# WS2811_Relais.net
KiCad netlist of a schematic drawn in EAGLE
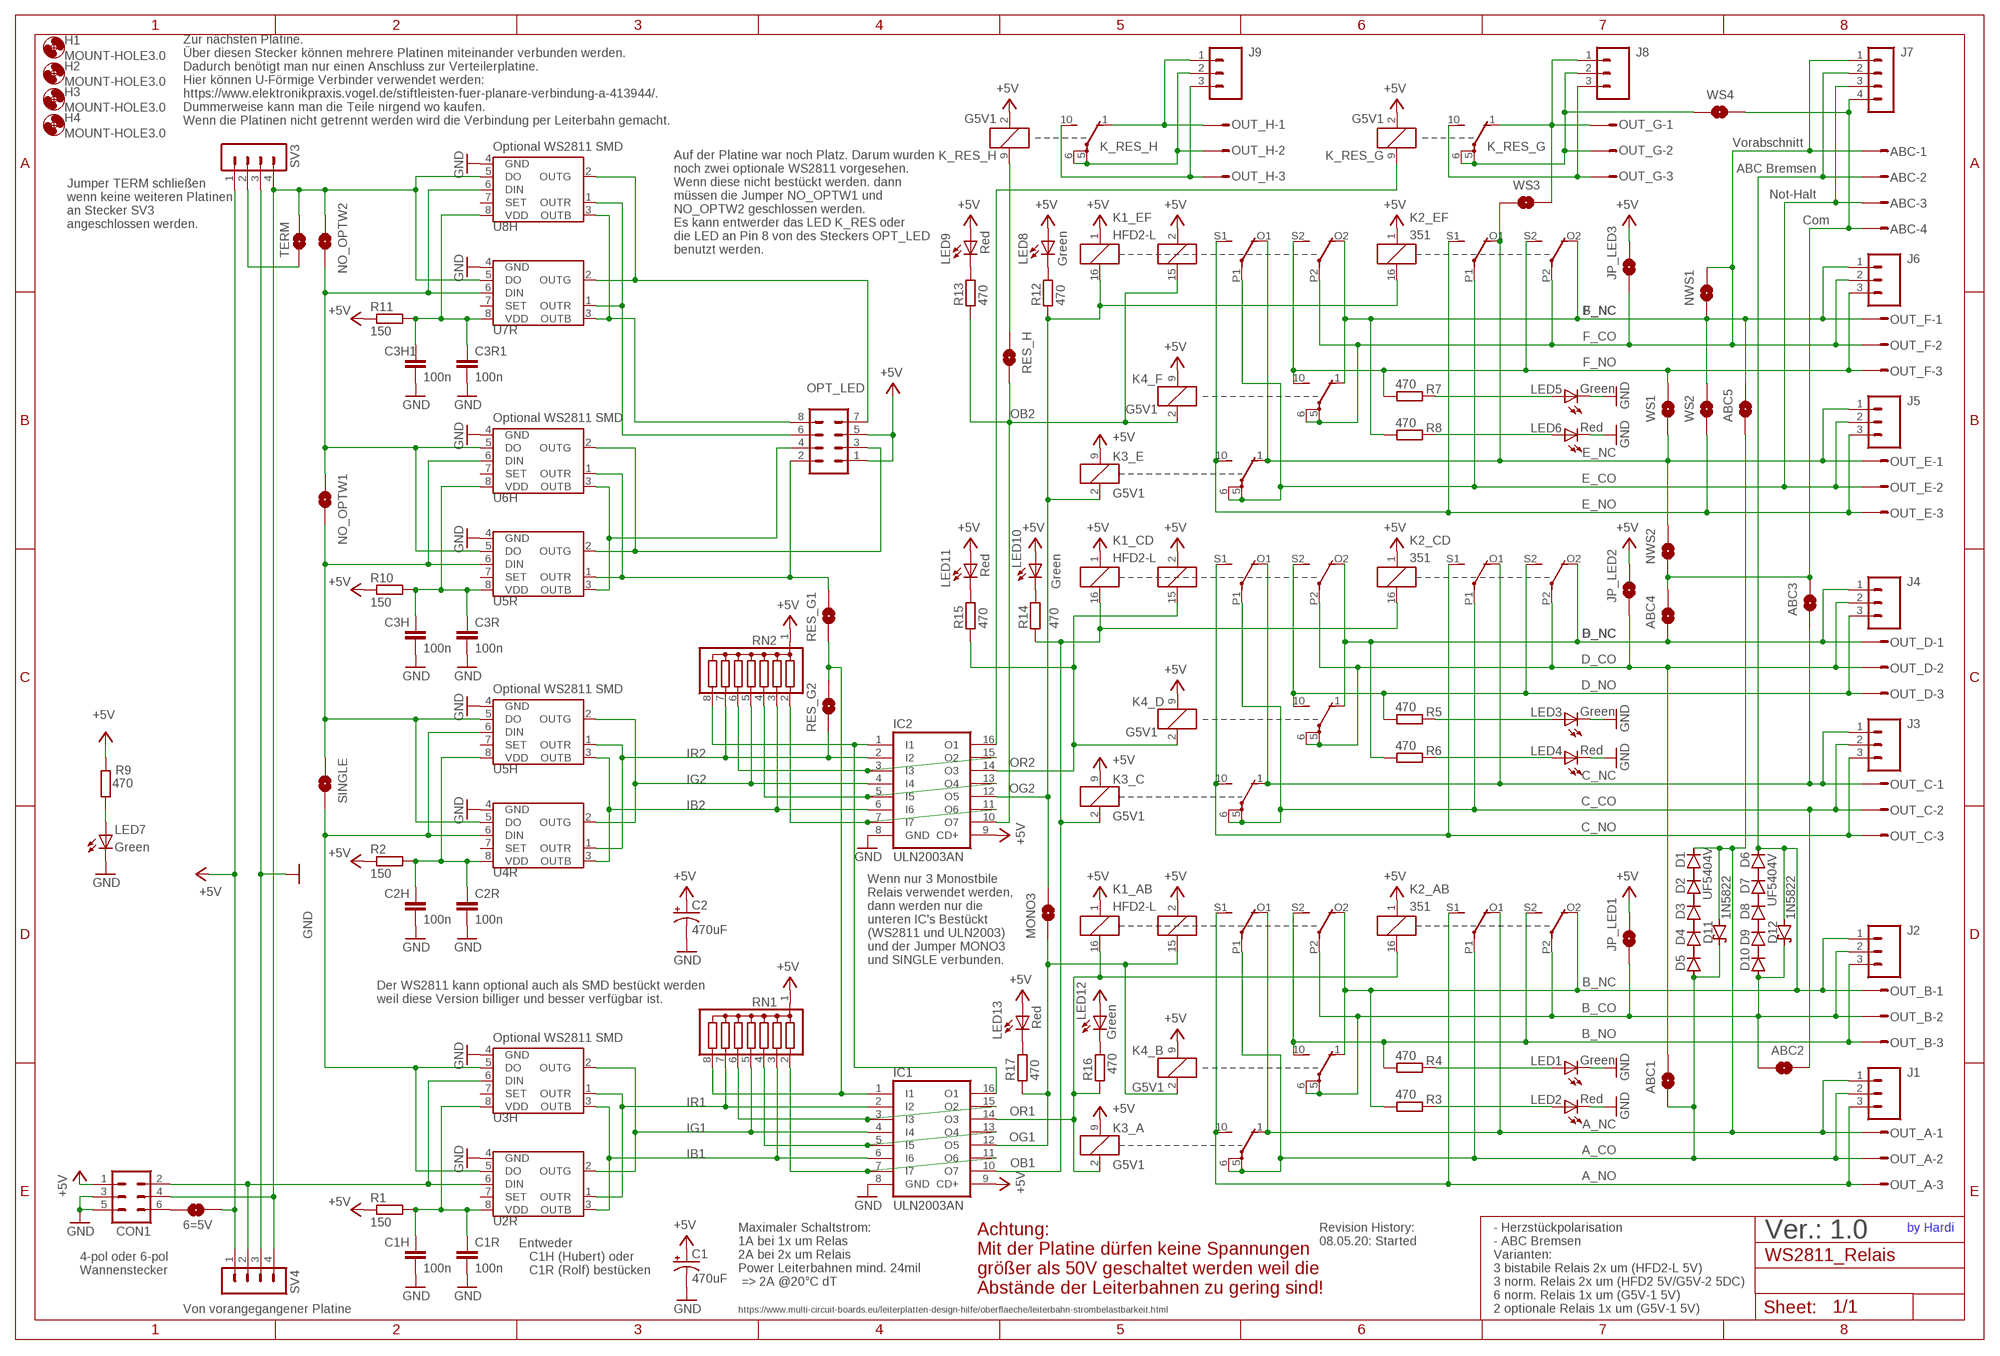
[diagram p0: schematic, sheet 1]

(export (version "E")
  (design (tool "Eeschema 10.0.6"))
  (components
    (comp (ref "6=5V")
      (value "SOLDERJUMPERNO")
      (footprint "eagle-import:SJ_2S-NO")
      (libsource (lib "eagle-import") (part "SOLDERJUMPERNO"))
    )
    (comp (ref "ABC")
      (value "STL1550-4ON_BOARD")
      (footprint "eagle-import:STL1550-4_ON_BOARD")
      (libsource (lib "eagle-import") (part "STL1550-4ON_BOARD"))
    )
    (comp (ref "ABC1")
      (value "SOLDERJUMPERNO")
      (footprint "eagle-import:SJ_2S-NO")
      (libsource (lib "eagle-import") (part "SOLDERJUMPERNO"))
    )
    (comp (ref "ABC2")
      (value "SOLDERJUMPERNO")
      (footprint "eagle-import:SJ_2S-NO")
      (libsource (lib "eagle-import") (part "SOLDERJUMPERNO"))
    )
    (comp (ref "ABC3")
      (value "SOLDERJUMPERNO")
      (footprint "eagle-import:SJ_2S-NO")
      (libsource (lib "eagle-import") (part "SOLDERJUMPERNO"))
    )
    (comp (ref "ABC4")
      (value "SOLDERJUMPERNO")
      (footprint "eagle-import:SJ_2S-NO")
      (libsource (lib "eagle-import") (part "SOLDERJUMPERNO"))
    )
    (comp (ref "ABC5")
      (value "SOLDERJUMPERNO")
      (footprint "eagle-import:SJ_2S-NO")
      (libsource (lib "eagle-import") (part "SOLDERJUMPERNO"))
    )
    (comp (ref "C1")
      (value "470uF")
      (footprint "eagle-import:SPARKFUN-CAPACITORS_CPOL-RADIAL-100UF-25V")
      (libsource (lib "eagle-import") (part "SPARKFUN-CAPACITORS_100UF-25V-20%(PTH)"))
    )
    (comp (ref "C1H")
      (value "100n")
      (footprint "eagle-import:C1206")
      (libsource (lib "eagle-import") (part "C-EUC1206"))
    )
    (comp (ref "C1R")
      (value "100n")
      (footprint "eagle-import:C025-024X044")
      (libsource (lib "eagle-import") (part "C-EU025-024X044"))
    )
    (comp (ref "C2")
      (value "470uF")
      (footprint "eagle-import:SPARKFUN-CAPACITORS_CPOL-RADIAL-100UF-25V")
      (libsource (lib "eagle-import") (part "SPARKFUN-CAPACITORS_100UF-25V-20%(PTH)"))
    )
    (comp (ref "C2H")
      (value "100n")
      (footprint "eagle-import:C1206")
      (libsource (lib "eagle-import") (part "C-EUC1206"))
    )
    (comp (ref "C2R")
      (value "100n")
      (footprint "eagle-import:C025-024X044")
      (libsource (lib "eagle-import") (part "C-EU025-024X044"))
    )
    (comp (ref "C3H")
      (value "100n")
      (footprint "eagle-import:C1206")
      (libsource (lib "eagle-import") (part "C-EUC1206"))
    )
    (comp (ref "C3H1")
      (value "100n")
      (footprint "eagle-import:C1206")
      (libsource (lib "eagle-import") (part "C-EUC1206"))
    )
    (comp (ref "C3R")
      (value "100n")
      (footprint "eagle-import:C025-024X044")
      (libsource (lib "eagle-import") (part "C-EU025-024X044"))
    )
    (comp (ref "C3R1")
      (value "100n")
      (footprint "eagle-import:C025-024X044")
      (libsource (lib "eagle-import") (part "C-EU025-024X044"))
    )
    (comp (ref "CON1")
      (value "ML6")
      (footprint "eagle-import:ML6")
      (libsource (lib "eagle-import") (part "ML6"))
    )
    (comp (ref "D1")
      (value "UF5404V")
      (footprint "eagle-import:DO201-15-V")
      (libsource (lib "eagle-import") (part "UF5404V"))
    )
    (comp (ref "D2")
      (value "UF5404V")
      (footprint "eagle-import:DO201-15-V")
      (libsource (lib "eagle-import") (part "UF5404V"))
    )
    (comp (ref "D3")
      (value "UF5404V")
      (footprint "eagle-import:DO201-15-V")
      (libsource (lib "eagle-import") (part "UF5404V"))
    )
    (comp (ref "D4")
      (value "UF5404V")
      (footprint "eagle-import:DO201-15-V")
      (libsource (lib "eagle-import") (part "UF5404V"))
    )
    (comp (ref "D5")
      (value "UF5404V")
      (footprint "eagle-import:DO201-15-V")
      (libsource (lib "eagle-import") (part "UF5404V"))
    )
    (comp (ref "D6")
      (value "UF5404V")
      (footprint "eagle-import:DO201-15-V")
      (libsource (lib "eagle-import") (part "UF5404V"))
    )
    (comp (ref "D7")
      (value "UF5404V")
      (footprint "eagle-import:DO201-15-V")
      (libsource (lib "eagle-import") (part "UF5404V"))
    )
    (comp (ref "D8")
      (value "UF5404V")
      (footprint "eagle-import:DO201-15-V")
      (libsource (lib "eagle-import") (part "UF5404V"))
    )
    (comp (ref "D9")
      (value "UF5404V")
      (footprint "eagle-import:DO201-15-V")
      (libsource (lib "eagle-import") (part "UF5404V"))
    )
    (comp (ref "D10")
      (value "UF5404V")
      (footprint "eagle-import:DO201-15-V")
      (libsource (lib "eagle-import") (part "UF5404V"))
    )
    (comp (ref "D11")
      (value "1N5822")
      (footprint "eagle-import:DO41-7.6")
      (libsource (lib "eagle-import") (part "1N5822"))
    )
    (comp (ref "D12")
      (value "1N5822")
      (footprint "eagle-import:DO41-7.6")
      (libsource (lib "eagle-import") (part "1N5822"))
    )
    (comp (ref "H1")
      (value "MOUNT-HOLE3.0")
      (footprint "eagle-import:3,0")
      (libsource (lib "eagle-import") (part "MOUNT-HOLE3.0"))
    )
    (comp (ref "H2")
      (value "MOUNT-HOLE3.0")
      (footprint "eagle-import:3,0")
      (libsource (lib "eagle-import") (part "MOUNT-HOLE3.0"))
    )
    (comp (ref "H3")
      (value "MOUNT-HOLE3.0")
      (footprint "eagle-import:3,0")
      (libsource (lib "eagle-import") (part "MOUNT-HOLE3.0"))
    )
    (comp (ref "H4")
      (value "MOUNT-HOLE3.0")
      (footprint "eagle-import:3,0")
      (libsource (lib "eagle-import") (part "MOUNT-HOLE3.0"))
    )
    (comp (ref "IC1")
      (value "ULN2003AN")
      (footprint "eagle-import:DIL16")
      (libsource (lib "eagle-import") (part "ULN2003AN"))
    )
    (comp (ref "IC2")
      (value "ULN2003AN")
      (footprint "eagle-import:DIL16")
      (libsource (lib "eagle-import") (part "ULN2003AN"))
    )
    (comp (ref "J1")
      (value "M03PTH")
      (footprint "eagle-import:1X03")
      (libsource (lib "eagle-import") (part "M03PTH"))
    )
    (comp (ref "J2")
      (value "M03PTH")
      (footprint "eagle-import:1X03")
      (libsource (lib "eagle-import") (part "M03PTH"))
    )
    (comp (ref "J3")
      (value "M03PTH")
      (footprint "eagle-import:1X03")
      (libsource (lib "eagle-import") (part "M03PTH"))
    )
    (comp (ref "J4")
      (value "M03PTH")
      (footprint "eagle-import:1X03")
      (libsource (lib "eagle-import") (part "M03PTH"))
    )
    (comp (ref "J5")
      (value "M03PTH")
      (footprint "eagle-import:1X03")
      (libsource (lib "eagle-import") (part "M03PTH"))
    )
    (comp (ref "J6")
      (value "M03PTH")
      (footprint "eagle-import:1X03")
      (libsource (lib "eagle-import") (part "M03PTH"))
    )
    (comp (ref "J7")
      (value "MA04-1")
      (footprint "eagle-import:MA04-1")
      (libsource (lib "eagle-import") (part "MA04-1"))
    )
    (comp (ref "J8")
      (value "M03PTH")
      (footprint "eagle-import:1X03")
      (libsource (lib "eagle-import") (part "M03PTH"))
    )
    (comp (ref "J9")
      (value "M03PTH")
      (footprint "eagle-import:1X03")
      (libsource (lib "eagle-import") (part "M03PTH"))
    )
    (comp (ref "JP_LED1")
      (value "SOLDERJUMPERNO")
      (footprint "eagle-import:SJ_2S-NO")
      (libsource (lib "eagle-import") (part "SOLDERJUMPERNO"))
    )
    (comp (ref "JP_LED2")
      (value "SOLDERJUMPERNO")
      (footprint "eagle-import:SJ_2S-NO")
      (libsource (lib "eagle-import") (part "SOLDERJUMPERNO"))
    )
    (comp (ref "JP_LED3")
      (value "SOLDERJUMPERNO")
      (footprint "eagle-import:SJ_2S-NO")
      (libsource (lib "eagle-import") (part "SOLDERJUMPERNO"))
    )
    (comp (ref "K1_AB")
      (value "HFD2-L")
      (footprint "eagle-import:HFD2-L")
      (libsource (lib "eagle-import") (part "HFD2-L"))
    )
    (comp (ref "K1_CD")
      (value "HFD2-L")
      (footprint "eagle-import:HFD2-L")
      (libsource (lib "eagle-import") (part "HFD2-L"))
    )
    (comp (ref "K1_EF")
      (value "HFD2-L")
      (footprint "eagle-import:HFD2-L")
      (libsource (lib "eagle-import") (part "HFD2-L"))
    )
    (comp (ref "K2_AB")
      (value "351")
      (footprint "eagle-import:351")
      (libsource (lib "eagle-import") (part "351"))
    )
    (comp (ref "K2_CD")
      (value "351")
      (footprint "eagle-import:351")
      (libsource (lib "eagle-import") (part "351"))
    )
    (comp (ref "K2_EF")
      (value "351")
      (footprint "eagle-import:351")
      (libsource (lib "eagle-import") (part "351"))
    )
    (comp (ref "K3_A")
      (value "G5V1")
      (footprint "eagle-import:G5V1")
      (fields (field (name "MPN") "G5V-1-DC24"))
      (libsource (lib "eagle-import") (part "G5V1"))
    )
    (comp (ref "K3_C")
      (value "G5V1")
      (footprint "eagle-import:G5V1")
      (fields (field (name "MPN") "G5V-1-DC24"))
      (libsource (lib "eagle-import") (part "G5V1"))
    )
    (comp (ref "K3_E")
      (value "G5V1")
      (footprint "eagle-import:G5V1")
      (fields (field (name "MPN") "G5V-1-DC24"))
      (libsource (lib "eagle-import") (part "G5V1"))
    )
    (comp (ref "K4_B")
      (value "G5V1")
      (footprint "eagle-import:G5V1")
      (fields (field (name "MPN") "G5V-1-DC24"))
      (libsource (lib "eagle-import") (part "G5V1"))
    )
    (comp (ref "K4_D")
      (value "G5V1")
      (footprint "eagle-import:G5V1")
      (fields (field (name "MPN") "G5V-1-DC24"))
      (libsource (lib "eagle-import") (part "G5V1"))
    )
    (comp (ref "K4_F")
      (value "G5V1")
      (footprint "eagle-import:G5V1")
      (fields (field (name "MPN") "G5V-1-DC24"))
      (libsource (lib "eagle-import") (part "G5V1"))
    )
    (comp (ref "K_RES_G")
      (value "G5V1")
      (footprint "eagle-import:G5V1")
      (fields (field (name "MPN") "G5V-1-DC24"))
      (libsource (lib "eagle-import") (part "G5V1"))
    )
    (comp (ref "K_RES_H")
      (value "G5V1")
      (footprint "eagle-import:G5V1")
      (fields (field (name "MPN") "G5V-1-DC24"))
      (libsource (lib "eagle-import") (part "G5V1"))
    )
    (comp (ref "LED1")
      (value "Green")
      (footprint "eagle-import:LED3MM")
      (libsource (lib "eagle-import") (part "LED3MM"))
    )
    (comp (ref "LED2")
      (value "Red")
      (footprint "eagle-import:LED3MM")
      (libsource (lib "eagle-import") (part "LED3MM"))
    )
    (comp (ref "LED3")
      (value "Green")
      (footprint "eagle-import:LED3MM")
      (libsource (lib "eagle-import") (part "LED3MM"))
    )
    (comp (ref "LED4")
      (value "Red")
      (footprint "eagle-import:LED3MM")
      (libsource (lib "eagle-import") (part "LED3MM"))
    )
    (comp (ref "LED5")
      (value "Green")
      (footprint "eagle-import:LED3MM")
      (libsource (lib "eagle-import") (part "LED3MM"))
    )
    (comp (ref "LED6")
      (value "Red")
      (footprint "eagle-import:LED3MM")
      (libsource (lib "eagle-import") (part "LED3MM"))
    )
    (comp (ref "LED7")
      (value "Green")
      (footprint "eagle-import:LED3MM")
      (libsource (lib "eagle-import") (part "LED3MM"))
    )
    (comp (ref "LED8")
      (value "Green")
      (footprint "eagle-import:LED3MM")
      (libsource (lib "eagle-import") (part "LED3MM"))
    )
    (comp (ref "LED9")
      (value "Red")
      (footprint "eagle-import:LED3MM")
      (libsource (lib "eagle-import") (part "LED3MM"))
    )
    (comp (ref "LED10")
      (value "Green")
      (footprint "eagle-import:LED3MM")
      (libsource (lib "eagle-import") (part "LED3MM"))
    )
    (comp (ref "LED11")
      (value "Red")
      (footprint "eagle-import:LED3MM")
      (libsource (lib "eagle-import") (part "LED3MM"))
    )
    (comp (ref "LED12")
      (value "Green")
      (footprint "eagle-import:LED3MM")
      (libsource (lib "eagle-import") (part "LED3MM"))
    )
    (comp (ref "LED13")
      (value "Red")
      (footprint "eagle-import:LED3MM")
      (libsource (lib "eagle-import") (part "LED3MM"))
    )
    (comp (ref "MONO3")
      (value "SOLDERJUMPERNO")
      (footprint "eagle-import:SJ_2S-NO")
      (libsource (lib "eagle-import") (part "SOLDERJUMPERNO"))
    )
    (comp (ref "NO_OPTW1")
      (value "SOLDERJUMPERNO")
      (footprint "eagle-import:SJ_2S-NO")
      (libsource (lib "eagle-import") (part "SOLDERJUMPERNO"))
    )
    (comp (ref "NO_OPTW2")
      (value "SOLDERJUMPERNO")
      (footprint "eagle-import:SJ_2S-NO")
      (libsource (lib "eagle-import") (part "SOLDERJUMPERNO"))
    )
    (comp (ref "NWS1")
      (value "SOLDERJUMPERNO")
      (footprint "eagle-import:SJ_2S-NO")
      (libsource (lib "eagle-import") (part "SOLDERJUMPERNO"))
    )
    (comp (ref "NWS2")
      (value "SOLDERJUMPERNO")
      (footprint "eagle-import:SJ_2S-NO")
      (libsource (lib "eagle-import") (part "SOLDERJUMPERNO"))
    )
    (comp (ref "OPT_LED")
      (value "CON-HARTING-ML_ML08")
      (footprint "eagle-import:CON-HARTING-ML_ML08")
      (libsource (lib "eagle-import") (part "CON-HARTING-ML_ML08"))
    )
    (comp (ref "OUT_A")
      (value "STL1550-3")
      (footprint "eagle-import:STL1550-3_ON_BOARD")
      (libsource (lib "eagle-import") (part "STL1550-3"))
    )
    (comp (ref "OUT_B")
      (value "STL1550-3")
      (footprint "eagle-import:STL1550-3_ON_BOARD")
      (libsource (lib "eagle-import") (part "STL1550-3"))
    )
    (comp (ref "OUT_C")
      (value "STL1550-3")
      (footprint "eagle-import:STL1550-3_ON_BOARD")
      (libsource (lib "eagle-import") (part "STL1550-3"))
    )
    (comp (ref "OUT_D")
      (value "STL1550-3")
      (footprint "eagle-import:STL1550-3_ON_BOARD")
      (libsource (lib "eagle-import") (part "STL1550-3"))
    )
    (comp (ref "OUT_E")
      (value "STL1550-3")
      (footprint "eagle-import:STL1550-3_ON_BOARD")
      (libsource (lib "eagle-import") (part "STL1550-3"))
    )
    (comp (ref "OUT_F")
      (value "STL1550-3")
      (footprint "eagle-import:STL1550-3_ON_BOARD")
      (libsource (lib "eagle-import") (part "STL1550-3"))
    )
    (comp (ref "OUT_G")
      (value "STL1550-3")
      (footprint "eagle-import:STL1550-3_ON_BOARD")
      (libsource (lib "eagle-import") (part "STL1550-3"))
    )
    (comp (ref "OUT_H")
      (value "STL1550-3")
      (footprint "eagle-import:STL1550-3_ON_BOARD")
      (libsource (lib "eagle-import") (part "STL1550-3"))
    )
    (comp (ref "R1")
      (value "150")
      (footprint "eagle-import:RCL_0207_2V")
      (libsource (lib "eagle-import") (part "RCL_R-EU_0207/2V"))
    )
    (comp (ref "R2")
      (value "150")
      (footprint "eagle-import:RCL_0207_2V")
      (libsource (lib "eagle-import") (part "RCL_R-EU_0207/2V"))
    )
    (comp (ref "R3")
      (value "470")
      (footprint "eagle-import:0204_2V")
      (libsource (lib "eagle-import") (part "R0204/2V"))
    )
    (comp (ref "R4")
      (value "470")
      (footprint "eagle-import:0204_2V")
      (libsource (lib "eagle-import") (part "R0204/2V"))
    )
    (comp (ref "R5")
      (value "470")
      (footprint "eagle-import:0204_2V")
      (libsource (lib "eagle-import") (part "R0204/2V"))
    )
    (comp (ref "R6")
      (value "470")
      (footprint "eagle-import:0204_2V")
      (libsource (lib "eagle-import") (part "R0204/2V"))
    )
    (comp (ref "R7")
      (value "470")
      (footprint "eagle-import:0204_2V")
      (libsource (lib "eagle-import") (part "R0204/2V"))
    )
    (comp (ref "R8")
      (value "470")
      (footprint "eagle-import:0204_2V")
      (libsource (lib "eagle-import") (part "R0204/2V"))
    )
    (comp (ref "R9")
      (value "470")
      (footprint "eagle-import:0204_2V")
      (libsource (lib "eagle-import") (part "R0204/2V"))
    )
    (comp (ref "R10")
      (value "150")
      (footprint "eagle-import:RCL_0207_2V")
      (libsource (lib "eagle-import") (part "RCL_R-EU_0207/2V"))
    )
    (comp (ref "R11")
      (value "150")
      (footprint "eagle-import:RCL_0207_2V")
      (libsource (lib "eagle-import") (part "RCL_R-EU_0207/2V"))
    )
    (comp (ref "R12")
      (value "470")
      (footprint "eagle-import:0204_2V")
      (libsource (lib "eagle-import") (part "R0204/2V"))
    )
    (comp (ref "R13")
      (value "470")
      (footprint "eagle-import:0204_2V")
      (libsource (lib "eagle-import") (part "R0204/2V"))
    )
    (comp (ref "R14")
      (value "470")
      (footprint "eagle-import:0204_2V")
      (libsource (lib "eagle-import") (part "R0204/2V"))
    )
    (comp (ref "R15")
      (value "470")
      (footprint "eagle-import:0204_2V")
      (libsource (lib "eagle-import") (part "R0204/2V"))
    )
    (comp (ref "R16")
      (value "470")
      (footprint "eagle-import:0204_2V")
      (libsource (lib "eagle-import") (part "R0204/2V"))
    )
    (comp (ref "R17")
      (value "470")
      (footprint "eagle-import:0204_2V")
      (libsource (lib "eagle-import") (part "R0204/2V"))
    )
    (comp (ref "RES_G1")
      (value "SOLDERJUMPERNO")
      (footprint "eagle-import:SJ_2S-NO")
      (libsource (lib "eagle-import") (part "SOLDERJUMPERNO"))
    )
    (comp (ref "RES_G2")
      (value "SOLDERJUMPERNO")
      (footprint "eagle-import:SJ_2S-NO")
      (libsource (lib "eagle-import") (part "SOLDERJUMPERNO"))
    )
    (comp (ref "RES_H")
      (value "SOLDERJUMPERNO")
      (footprint "eagle-import:SJ_2S-NO")
      (libsource (lib "eagle-import") (part "SOLDERJUMPERNO"))
    )
    (comp (ref "RN1")
      (value "G07R")
      (footprint "eagle-import:SIL8")
      (libsource (lib "eagle-import") (part "G07R"))
    )
    (comp (ref "RN2")
      (value "G07R")
      (footprint "eagle-import:SIL8")
      (libsource (lib "eagle-import") (part "G07R"))
    )
    (comp (ref "SINGLE")
      (value "SOLDERJUMPERNO")
      (footprint "eagle-import:SJ_2S-NO")
      (libsource (lib "eagle-import") (part "SOLDERJUMPERNO"))
    )
    (comp (ref "SV3")
      (value "MA04-1")
      (footprint "eagle-import:MA04-1")
      (libsource (lib "eagle-import") (part "MA04-1"))
    )
    (comp (ref "SV4")
      (value "MA04-1")
      (footprint "eagle-import:MA04-1")
      (libsource (lib "eagle-import") (part "MA04-1"))
    )
    (comp (ref "TERM")
      (value "SOLDERJUMPERNO")
      (footprint "eagle-import:SJ_2S-NO")
      (libsource (lib "eagle-import") (part "SOLDERJUMPERNO"))
    )
    (comp (ref "U2R")
      (value "WS2811")
      (footprint "eagle-import:S3PO_MODUL_WS2811_SOUND_MP3-TF-16P_WS2811_AND_ATTINY_WS2811_DIP08")
      (libsource (lib "eagle-import") (part "S3PO_MODUL_WS2811_SOUND_MP3-TF-16P_WS2811_AND_ATTINY_WS2811-ICTINY45-20-DIP"))
    )
    (comp (ref "U3H")
      (value "WS2811 SOT-8")
      (footprint "eagle-import:SOP8")
      (libsource (lib "eagle-import") (part "S3PO_MODUL_WS2811_SOUND_MP3-TF-16P_WS2811_AND_ATTINY_WS2811-ICSOP8"))
    )
    (comp (ref "U4R")
      (value "WS2811")
      (footprint "eagle-import:S3PO_MODUL_WS2811_SOUND_MP3-TF-16P_WS2811_AND_ATTINY_WS2811_DIP08")
      (libsource (lib "eagle-import") (part "S3PO_MODUL_WS2811_SOUND_MP3-TF-16P_WS2811_AND_ATTINY_WS2811-ICTINY45-20-DIP"))
    )
    (comp (ref "U5H")
      (value "WS2811 SOT-8")
      (footprint "eagle-import:SOP8")
      (libsource (lib "eagle-import") (part "S3PO_MODUL_WS2811_SOUND_MP3-TF-16P_WS2811_AND_ATTINY_WS2811-ICSOP8"))
    )
    (comp (ref "U5R")
      (value "WS2811")
      (footprint "eagle-import:S3PO_MODUL_WS2811_SOUND_MP3-TF-16P_WS2811_AND_ATTINY_WS2811_DIP08")
      (libsource (lib "eagle-import") (part "S3PO_MODUL_WS2811_SOUND_MP3-TF-16P_WS2811_AND_ATTINY_WS2811-ICTINY45-20-DIP"))
    )
    (comp (ref "U6H")
      (value "WS2811 SOT-8")
      (footprint "eagle-import:SOP8")
      (libsource (lib "eagle-import") (part "S3PO_MODUL_WS2811_SOUND_MP3-TF-16P_WS2811_AND_ATTINY_WS2811-ICSOP8"))
    )
    (comp (ref "U7R")
      (value "WS2811")
      (footprint "eagle-import:S3PO_MODUL_WS2811_SOUND_MP3-TF-16P_WS2811_AND_ATTINY_WS2811_DIP08")
      (libsource (lib "eagle-import") (part "S3PO_MODUL_WS2811_SOUND_MP3-TF-16P_WS2811_AND_ATTINY_WS2811-ICTINY45-20-DIP"))
    )
    (comp (ref "U8H")
      (value "WS2811 SOT-8")
      (footprint "eagle-import:SOP8")
      (libsource (lib "eagle-import") (part "S3PO_MODUL_WS2811_SOUND_MP3-TF-16P_WS2811_AND_ATTINY_WS2811-ICSOP8"))
    )
    (comp (ref "WS1")
      (value "SOLDERJUMPERNO")
      (footprint "eagle-import:SJ_2S-NO")
      (libsource (lib "eagle-import") (part "SOLDERJUMPERNO"))
    )
    (comp (ref "WS2")
      (value "SOLDERJUMPERNO")
      (footprint "eagle-import:SJ_2S-NO")
      (libsource (lib "eagle-import") (part "SOLDERJUMPERNO"))
    )
    (comp (ref "WS3")
      (value "SOLDERJUMPERNO")
      (footprint "eagle-import:SJ_2S-NO")
      (libsource (lib "eagle-import") (part "SOLDERJUMPERNO"))
    )
    (comp (ref "WS4")
      (value "SOLDERJUMPERNO")
      (footprint "eagle-import:SJ_2S-NO")
      (libsource (lib "eagle-import") (part "SOLDERJUMPERNO"))
    )
  )
  (nets
    (net (code "1") (name "+5V") (class "Default")
      (node (ref "6=5V") (pin "2") (pinfunction "2_2") (pintype "passive"))
      (node (ref "C1") (pin "1") (pinfunction "+_1") (pintype "passive"))
      (node (ref "C2") (pin "1") (pinfunction "+_1") (pintype "passive"))
      (node (ref "CON1") (pin "1") (pinfunction "1_1") (pintype "passive"))
      (node (ref "IC1") (pin "9") (pinfunction "CD+_9") (pintype "passive"))
      (node (ref "IC2") (pin "9") (pinfunction "CD+_9") (pintype "passive"))
      (node (ref "JP_LED1") (pin "2") (pinfunction "2_2") (pintype "passive"))
      (node (ref "JP_LED2") (pin "2") (pinfunction "2_2") (pintype "passive"))
      (node (ref "JP_LED3") (pin "2") (pinfunction "2_2") (pintype "passive"))
      (node (ref "K1_AB") (pin "1") (pinfunction "1_1") (pintype "passive"))
      (node (ref "K1_AB") (pin "2") (pinfunction "3_2") (pintype "passive"))
      (node (ref "K1_CD") (pin "1") (pinfunction "1_1") (pintype "passive"))
      (node (ref "K1_CD") (pin "2") (pinfunction "3_2") (pintype "passive"))
      (node (ref "K1_EF") (pin "1") (pinfunction "1_1") (pintype "passive"))
      (node (ref "K1_EF") (pin "2") (pinfunction "3_2") (pintype "passive"))
      (node (ref "K2_AB") (pin "1") (pinfunction "1_1") (pintype "passive"))
      (node (ref "K2_CD") (pin "1") (pinfunction "1_1") (pintype "passive"))
      (node (ref "K2_EF") (pin "1") (pinfunction "1_1") (pintype "passive"))
      (node (ref "K3_A") (pin "9") (pinfunction "2_9") (pintype "passive"))
      (node (ref "K3_C") (pin "9") (pinfunction "2_9") (pintype "passive"))
      (node (ref "K3_E") (pin "9") (pinfunction "2_9") (pintype "passive"))
      (node (ref "K4_B") (pin "9") (pinfunction "2_9") (pintype "passive"))
      (node (ref "K4_D") (pin "9") (pinfunction "2_9") (pintype "passive"))
      (node (ref "K4_F") (pin "9") (pinfunction "2_9") (pintype "passive"))
      (node (ref "K_RES_G") (pin "2") (pinfunction "1_2") (pintype "passive"))
      (node (ref "K_RES_H") (pin "2") (pinfunction "1_2") (pintype "passive"))
      (node (ref "LED10") (pin "A") (pinfunction "A_A") (pintype "passive"))
      (node (ref "LED11") (pin "A") (pinfunction "A_A") (pintype "passive"))
      (node (ref "LED12") (pin "A") (pinfunction "A_A") (pintype "passive"))
      (node (ref "LED13") (pin "A") (pinfunction "A_A") (pintype "passive"))
      (node (ref "LED8") (pin "A") (pinfunction "A_A") (pintype "passive"))
      (node (ref "LED9") (pin "A") (pinfunction "A_A") (pintype "passive"))
      (node (ref "OPT_LED") (pin "1") (pinfunction "1_1") (pintype "passive"))
      (node (ref "OPT_LED") (pin "5") (pinfunction "5_5") (pintype "passive"))
      (node (ref "R1") (pin "1") (pinfunction "1_1") (pintype "passive"))
      (node (ref "R10") (pin "1") (pinfunction "1_1") (pintype "passive"))
      (node (ref "R11") (pin "1") (pinfunction "1_1") (pintype "passive"))
      (node (ref "R2") (pin "1") (pinfunction "1_1") (pintype "passive"))
      (node (ref "R9") (pin "1") (pinfunction "1_1") (pintype "passive"))
      (node (ref "RN1") (pin "1") (pinfunction "1_1") (pintype "passive"))
      (node (ref "RN2") (pin "1") (pinfunction "1_1") (pintype "passive"))
      (node (ref "SV3") (pin "1") (pinfunction "1_1") (pintype "passive"))
      (node (ref "SV4") (pin "1") (pinfunction "1_1") (pintype "passive"))
    )
    (net (code "2") (name "/A_CO") (class "Default")
      (node (ref "ABC1") (pin "1") (pinfunction "1_1") (pintype "passive"))
      (node (ref "D11") (pin "C") (pinfunction "C_C") (pintype "passive"))
      (node (ref "D5") (pin "A") (pinfunction "A_A") (pintype "passive"))
      (node (ref "J1") (pin "2") (pinfunction "2_2") (pintype "passive"))
      (node (ref "K1_AB") (pin "P1") (pinfunction "P_P1") (pintype "passive"))
      (node (ref "K2_AB") (pin "P1") (pinfunction "P_P1") (pintype "passive"))
      (node (ref "K3_A") (pin "5") (pinfunction "P_5") (pintype "passive"))
      (node (ref "K3_A") (pin "6") (pinfunction "P_6") (pintype "passive"))
      (node (ref "OUT_A") (pin "2") (pinfunction "S_2") (pintype "passive"))
    )
    (net (code "3") (name "/A_NC") (class "Default")
      (node (ref "ABC5") (pin "2") (pinfunction "2_2") (pintype "passive"))
      (node (ref "D1") (pin "C") (pinfunction "C_C") (pintype "passive"))
      (node (ref "D11") (pin "A") (pinfunction "A_A") (pintype "passive"))
      (node (ref "J1") (pin "1") (pinfunction "1_1") (pintype "passive"))
      (node (ref "K1_AB") (pin "O1") (pinfunction "O_O1") (pintype "passive"))
      (node (ref "K2_AB") (pin "O1") (pinfunction "O_O1") (pintype "passive"))
      (node (ref "K3_A") (pin "1") (pinfunction "O_1") (pintype "passive"))
      (node (ref "OUT_A") (pin "1") (pinfunction "S_1") (pintype "passive"))
    )
    (net (code "4") (name "/A_NO") (class "Default")
      (node (ref "J1") (pin "3") (pinfunction "3_3") (pintype "passive"))
      (node (ref "K1_AB") (pin "S1") (pinfunction "S_S1") (pintype "passive"))
      (node (ref "K2_AB") (pin "S1") (pinfunction "S_S1") (pintype "passive"))
      (node (ref "K3_A") (pin "10") (pinfunction "S_10") (pintype "passive"))
      (node (ref "OUT_A") (pin "3") (pinfunction "S_3") (pintype "passive"))
    )
    (net (code "5") (name "/B_CO") (class "Default")
      (node (ref "ABC2") (pin "1") (pinfunction "1_1") (pintype "passive"))
      (node (ref "D10") (pin "A") (pinfunction "A_A") (pintype "passive"))
      (node (ref "D12") (pin "C") (pinfunction "C_C") (pintype "passive"))
      (node (ref "J2") (pin "2") (pinfunction "2_2") (pintype "passive"))
      (node (ref "JP_LED1") (pin "1") (pinfunction "1_1") (pintype "passive"))
      (node (ref "K1_AB") (pin "P2") (pinfunction "P_P2") (pintype "passive"))
      (node (ref "K2_AB") (pin "P2") (pinfunction "P_P2") (pintype "passive"))
      (node (ref "K4_B") (pin "5") (pinfunction "P_5") (pintype "passive"))
      (node (ref "K4_B") (pin "6") (pinfunction "P_6") (pintype "passive"))
      (node (ref "OUT_B") (pin "2") (pinfunction "S_2") (pintype "passive"))
    )
    (net (code "6") (name "/B_NC") (class "Default")
      (node (ref "ABC") (pin "2") (pinfunction "S_2") (pintype "passive"))
      (node (ref "D12") (pin "A") (pinfunction "A_A") (pintype "passive"))
      (node (ref "D6") (pin "C") (pinfunction "C_C") (pintype "passive"))
      (node (ref "J2") (pin "1") (pinfunction "1_1") (pintype "passive"))
      (node (ref "J7") (pin "2") (pinfunction "2_2") (pintype "passive"))
      (node (ref "K1_AB") (pin "O2") (pinfunction "O_O2") (pintype "passive"))
      (node (ref "K2_AB") (pin "O2") (pinfunction "O_O2") (pintype "passive"))
      (node (ref "K4_B") (pin "1") (pinfunction "O_1") (pintype "passive"))
      (node (ref "OUT_B") (pin "1") (pinfunction "S_1") (pintype "passive"))
      (node (ref "R3") (pin "2") (pinfunction "2_2") (pintype "passive"))
    )
    (net (code "7") (name "/B_NO") (class "Default")
      (node (ref "J2") (pin "3") (pinfunction "3_3") (pintype "passive"))
      (node (ref "K1_AB") (pin "S2") (pinfunction "S_S2") (pintype "passive"))
      (node (ref "K2_AB") (pin "S2") (pinfunction "S_S2") (pintype "passive"))
      (node (ref "K4_B") (pin "10") (pinfunction "S_10") (pintype "passive"))
      (node (ref "OUT_B") (pin "3") (pinfunction "S_3") (pintype "passive"))
      (node (ref "R4") (pin "2") (pinfunction "2_2") (pintype "passive"))
    )
    (net (code "8") (name "/C_CO") (class "Default")
      (node (ref "ABC2") (pin "2") (pinfunction "2_2") (pintype "passive"))
      (node (ref "J3") (pin "2") (pinfunction "2_2") (pintype "passive"))
      (node (ref "K1_CD") (pin "P1") (pinfunction "P_P1") (pintype "passive"))
      (node (ref "K2_CD") (pin "P1") (pinfunction "P_P1") (pintype "passive"))
      (node (ref "K3_C") (pin "5") (pinfunction "P_5") (pintype "passive"))
      (node (ref "K3_C") (pin "6") (pinfunction "P_6") (pintype "passive"))
      (node (ref "OUT_C") (pin "2") (pinfunction "S_2") (pintype "passive"))
    )
    (net (code "9") (name "/C_NC") (class "Default")
      (node (ref "ABC3") (pin "2") (pinfunction "2_2") (pintype "passive"))
      (node (ref "J3") (pin "1") (pinfunction "1_1") (pintype "passive"))
      (node (ref "K1_CD") (pin "O1") (pinfunction "O_O1") (pintype "passive"))
      (node (ref "K2_CD") (pin "O1") (pinfunction "O_O1") (pintype "passive"))
      (node (ref "K3_C") (pin "1") (pinfunction "O_1") (pintype "passive"))
      (node (ref "OUT_C") (pin "1") (pinfunction "S_1") (pintype "passive"))
    )
    (net (code "10") (name "/C_NO") (class "Default")
      (node (ref "J3") (pin "3") (pinfunction "3_3") (pintype "passive"))
      (node (ref "K1_CD") (pin "S1") (pinfunction "S_S1") (pintype "passive"))
      (node (ref "K2_CD") (pin "S1") (pinfunction "S_S1") (pintype "passive"))
      (node (ref "K3_C") (pin "10") (pinfunction "S_10") (pintype "passive"))
      (node (ref "OUT_C") (pin "3") (pinfunction "S_3") (pintype "passive"))
    )
    (net (code "11") (name "/D_CO") (class "Default")
      (node (ref "ABC1") (pin "2") (pinfunction "2_2") (pintype "passive"))
      (node (ref "J4") (pin "2") (pinfunction "2_2") (pintype "passive"))
      (node (ref "JP_LED2") (pin "1") (pinfunction "1_1") (pintype "passive"))
      (node (ref "K1_CD") (pin "P2") (pinfunction "P_P2") (pintype "passive"))
      (node (ref "K2_CD") (pin "P2") (pinfunction "P_P2") (pintype "passive"))
      (node (ref "K4_D") (pin "5") (pinfunction "P_5") (pintype "passive"))
      (node (ref "K4_D") (pin "6") (pinfunction "P_6") (pintype "passive"))
      (node (ref "OUT_D") (pin "2") (pinfunction "S_2") (pintype "passive"))
    )
    (net (code "12") (name "/D_NC") (class "Default")
      (node (ref "ABC4") (pin "2") (pinfunction "2_2") (pintype "passive"))
      (node (ref "J4") (pin "1") (pinfunction "1_1") (pintype "passive"))
      (node (ref "K1_CD") (pin "O2") (pinfunction "O_O2") (pintype "passive"))
      (node (ref "K2_CD") (pin "O2") (pinfunction "O_O2") (pintype "passive"))
      (node (ref "K4_D") (pin "1") (pinfunction "O_1") (pintype "passive"))
      (node (ref "OUT_D") (pin "1") (pinfunction "S_1") (pintype "passive"))
      (node (ref "R6") (pin "2") (pinfunction "2_2") (pintype "passive"))
    )
    (net (code "13") (name "/D_NO") (class "Default")
      (node (ref "J4") (pin "3") (pinfunction "3_3") (pintype "passive"))
      (node (ref "K1_CD") (pin "S2") (pinfunction "S_S2") (pintype "passive"))
      (node (ref "K2_CD") (pin "S2") (pinfunction "S_S2") (pintype "passive"))
      (node (ref "K4_D") (pin "10") (pinfunction "S_10") (pintype "passive"))
      (node (ref "OUT_D") (pin "3") (pinfunction "S_3") (pintype "passive"))
      (node (ref "R5") (pin "2") (pinfunction "2_2") (pintype "passive"))
    )
    (net (code "14") (name "/E_CO") (class "Default")
      (node (ref "ABC") (pin "3") (pinfunction "S_3") (pintype "passive"))
      (node (ref "J5") (pin "2") (pinfunction "2_2") (pintype "passive"))
      (node (ref "J7") (pin "3") (pinfunction "3_3") (pintype "passive"))
      (node (ref "K1_EF") (pin "P1") (pinfunction "P_P1") (pintype "passive"))
      (node (ref "K2_EF") (pin "P1") (pinfunction "P_P1") (pintype "passive"))
      (node (ref "K3_E") (pin "5") (pinfunction "P_5") (pintype "passive"))
      (node (ref "K3_E") (pin "6") (pinfunction "P_6") (pintype "passive"))
      (node (ref "OUT_E") (pin "2") (pinfunction "S_2") (pintype "passive"))
    )
    (net (code "15") (name "/E_NC") (class "Default")
      (node (ref "J5") (pin "1") (pinfunction "1_1") (pintype "passive"))
      (node (ref "K1_EF") (pin "O1") (pinfunction "O_O1") (pintype "passive"))
      (node (ref "K2_EF") (pin "O1") (pinfunction "O_O1") (pintype "passive"))
      (node (ref "K3_E") (pin "1") (pinfunction "O_1") (pintype "passive"))
      (node (ref "NWS2") (pin "1") (pinfunction "1_1") (pintype "passive"))
      (node (ref "OUT_E") (pin "1") (pinfunction "S_1") (pintype "passive"))
      (node (ref "WS1") (pin "2") (pinfunction "2_2") (pintype "passive"))
      (node (ref "WS3") (pin "2") (pinfunction "2_2") (pintype "passive"))
    )
    (net (code "16") (name "/E_NO") (class "Default")
      (node (ref "J5") (pin "3") (pinfunction "3_3") (pintype "passive"))
      (node (ref "K1_EF") (pin "S1") (pinfunction "S_S1") (pintype "passive"))
      (node (ref "K2_EF") (pin "S1") (pinfunction "S_S1") (pintype "passive"))
      (node (ref "K3_E") (pin "10") (pinfunction "S_10") (pintype "passive"))
      (node (ref "OUT_E") (pin "3") (pinfunction "S_3") (pintype "passive"))
      (node (ref "WS2") (pin "2") (pinfunction "2_2") (pintype "passive"))
    )
    (net (code "17") (name "/F_CO") (class "Default")
      (node (ref "ABC") (pin "1") (pinfunction "S_1") (pintype "passive"))
      (node (ref "J6") (pin "2") (pinfunction "2_2") (pintype "passive"))
      (node (ref "J7") (pin "1") (pinfunction "1_1") (pintype "passive"))
      (node (ref "JP_LED3") (pin "1") (pinfunction "1_1") (pintype "passive"))
      (node (ref "K1_EF") (pin "P2") (pinfunction "P_P2") (pintype "passive"))
      (node (ref "K2_EF") (pin "P2") (pinfunction "P_P2") (pintype "passive"))
      (node (ref "K4_F") (pin "5") (pinfunction "P_5") (pintype "passive"))
      (node (ref "K4_F") (pin "6") (pinfunction "P_6") (pintype "passive"))
      (node (ref "NWS1") (pin "1") (pinfunction "1_1") (pintype "passive"))
      (node (ref "OUT_F") (pin "2") (pinfunction "S_2") (pintype "passive"))
    )
    (net (code "18") (name "/F_NC") (class "Default")
      (node (ref "ABC5") (pin "1") (pinfunction "1_1") (pintype "passive"))
      (node (ref "J6") (pin "1") (pinfunction "1_1") (pintype "passive"))
      (node (ref "K1_EF") (pin "O2") (pinfunction "O_O2") (pintype "passive"))
      (node (ref "K2_EF") (pin "O2") (pinfunction "O_O2") (pintype "passive"))
      (node (ref "K4_F") (pin "1") (pinfunction "O_1") (pintype "passive"))
      (node (ref "NWS1") (pin "2") (pinfunction "2_2") (pintype "passive"))
      (node (ref "OUT_F") (pin "1") (pinfunction "S_1") (pintype "passive"))
      (node (ref "R8") (pin "2") (pinfunction "2_2") (pintype "passive"))
      (node (ref "WS2") (pin "1") (pinfunction "1_1") (pintype "passive"))
    )
    (net (code "19") (name "/F_NO") (class "Default")
      (node (ref "J6") (pin "3") (pinfunction "3_3") (pintype "passive"))
      (node (ref "K1_EF") (pin "S2") (pinfunction "S_S2") (pintype "passive"))
      (node (ref "K2_EF") (pin "S2") (pinfunction "S_S2") (pintype "passive"))
      (node (ref "K4_F") (pin "10") (pinfunction "S_10") (pintype "passive"))
      (node (ref "OUT_F") (pin "3") (pinfunction "S_3") (pintype "passive"))
      (node (ref "R7") (pin "2") (pinfunction "2_2") (pintype "passive"))
      (node (ref "WS1") (pin "1") (pinfunction "1_1") (pintype "passive"))
    )
    (net (code "20") (name "/IB1") (class "Default")
      (node (ref "IC1") (pin "6") (pinfunction "I6_6") (pintype "input"))
      (node (ref "RN1") (pin "3") (pinfunction "3_3") (pintype "passive"))
      (node (ref "U2R") (pin "3") (pinfunction "OUTB_3") (pintype "open_collector"))
      (node (ref "U3H") (pin "3") (pinfunction "OUTB_3") (pintype "open_collector"))
    )
    (net (code "21") (name "/IB2") (class "Default")
      (node (ref "IC2") (pin "6") (pinfunction "I6_6") (pintype "input"))
      (node (ref "RN2") (pin "3") (pinfunction "3_3") (pintype "passive"))
      (node (ref "U4R") (pin "3") (pinfunction "OUTB_3") (pintype "open_collector"))
      (node (ref "U5H") (pin "3") (pinfunction "OUTB_3") (pintype "open_collector"))
    )
    (net (code "22") (name "/IG1") (class "Default")
      (node (ref "IC1") (pin "4") (pinfunction "I4_4") (pintype "input"))
      (node (ref "RN1") (pin "5") (pinfunction "5_5") (pintype "passive"))
      (node (ref "U2R") (pin "2") (pinfunction "OUTG_2") (pintype "open_collector"))
      (node (ref "U3H") (pin "2") (pinfunction "OUTG_2") (pintype "open_collector"))
    )
    (net (code "23") (name "/IG2") (class "Default")
      (node (ref "IC2") (pin "4") (pinfunction "I4_4") (pintype "input"))
      (node (ref "RN2") (pin "5") (pinfunction "5_5") (pintype "passive"))
      (node (ref "U4R") (pin "2") (pinfunction "OUTG_2") (pintype "open_collector"))
      (node (ref "U5H") (pin "2") (pinfunction "OUTG_2") (pintype "open_collector"))
    )
    (net (code "24") (name "/IR1") (class "Default")
      (node (ref "IC1") (pin "2") (pinfunction "I2_2") (pintype "input"))
      (node (ref "RN1") (pin "7") (pinfunction "7_7") (pintype "passive"))
      (node (ref "U2R") (pin "1") (pinfunction "OUTR_1") (pintype "open_collector"))
      (node (ref "U3H") (pin "1") (pinfunction "OUTR_1") (pintype "open_collector"))
    )
    (net (code "25") (name "/IR2") (class "Default")
      (node (ref "IC2") (pin "2") (pinfunction "I2_2") (pintype "input"))
      (node (ref "RES_G2") (pin "2") (pinfunction "2_2") (pintype "passive"))
      (node (ref "RN2") (pin "7") (pinfunction "7_7") (pintype "passive"))
      (node (ref "U4R") (pin "1") (pinfunction "OUTR_1") (pintype "open_collector"))
      (node (ref "U5H") (pin "1") (pinfunction "OUTR_1") (pintype "open_collector"))
    )
    (net (code "26") (name "/OB1") (class "Default")
      (node (ref "IC1") (pin "10") (pinfunction "O7_10") (pintype "open_collector"))
      (node (ref "K1_CD") (pin "16") (pinfunction "2_16") (pintype "passive"))
      (node (ref "K2_CD") (pin "16") (pinfunction "2_16") (pintype "passive"))
      (node (ref "K3_C") (pin "2") (pinfunction "1_2") (pintype "passive"))
      (node (ref "R14") (pin "2") (pinfunction "2_2") (pintype "passive"))
    )
    (net (code "27") (name "/OB2") (class "Default")
      (node (ref "IC2") (pin "10") (pinfunction "O7_10") (pintype "open_collector"))
      (node (ref "K1_EF") (pin "15") (pinfunction "4_15") (pintype "passive"))
      (node (ref "K4_F") (pin "2") (pinfunction "1_2") (pintype "passive"))
      (node (ref "R13") (pin "2") (pinfunction "2_2") (pintype "passive"))
      (node (ref "RES_H") (pin "1") (pinfunction "1_1") (pintype "passive"))
    )
    (net (code "28") (name "/OG1") (class "Default")
      (node (ref "IC1") (pin "12") (pinfunction "O5_12") (pintype "open_collector"))
      (node (ref "K1_AB") (pin "15") (pinfunction "4_15") (pintype "passive"))
      (node (ref "K4_B") (pin "2") (pinfunction "1_2") (pintype "passive"))
      (node (ref "MONO3") (pin "2") (pinfunction "2_2") (pintype "passive"))
      (node (ref "R17") (pin "2") (pinfunction "2_2") (pintype "passive"))
    )
    (net (code "29") (name "/OG2") (class "Default")
      (node (ref "IC2") (pin "12") (pinfunction "O5_12") (pintype "open_collector"))
      (node (ref "K1_EF") (pin "16") (pinfunction "2_16") (pintype "passive"))
      (node (ref "K2_EF") (pin "16") (pinfunction "2_16") (pintype "passive"))
      (node (ref "K3_E") (pin "2") (pinfunction "1_2") (pintype "passive"))
      (node (ref "MONO3") (pin "1") (pinfunction "1_1") (pintype "passive"))
      (node (ref "R12") (pin "2") (pinfunction "2_2") (pintype "passive"))
    )
    (net (code "30") (name "/OR1") (class "Default")
      (node (ref "IC1") (pin "14") (pinfunction "O3_14") (pintype "open_collector"))
      (node (ref "K1_AB") (pin "16") (pinfunction "2_16") (pintype "passive"))
      (node (ref "K2_AB") (pin "16") (pinfunction "2_16") (pintype "passive"))
      (node (ref "K3_A") (pin "2") (pinfunction "1_2") (pintype "passive"))
      (node (ref "R16") (pin "2") (pinfunction "2_2") (pintype "passive"))
    )
    (net (code "31") (name "/OR2") (class "Default")
      (node (ref "IC2") (pin "14") (pinfunction "O3_14") (pintype "open_collector"))
      (node (ref "K1_CD") (pin "15") (pinfunction "4_15") (pintype "passive"))
      (node (ref "K4_D") (pin "2") (pinfunction "1_2") (pintype "passive"))
      (node (ref "R15") (pin "2") (pinfunction "2_2") (pintype "passive"))
    )
    (net (code "32") (name "GND") (class "Default")
      (node (ref "C1") (pin "2") (pinfunction "-_2") (pintype "passive"))
      (node (ref "C1H") (pin "2") (pinfunction "2_2") (pintype "passive"))
      (node (ref "C1R") (pin "2") (pinfunction "2_2") (pintype "passive"))
      (node (ref "C2") (pin "2") (pinfunction "-_2") (pintype "passive"))
      (node (ref "C2H") (pin "2") (pinfunction "2_2") (pintype "passive"))
      (node (ref "C2R") (pin "2") (pinfunction "2_2") (pintype "passive"))
      (node (ref "C3H") (pin "2") (pinfunction "2_2") (pintype "passive"))
      (node (ref "C3H1") (pin "2") (pinfunction "2_2") (pintype "passive"))
      (node (ref "C3R") (pin "2") (pinfunction "2_2") (pintype "passive"))
      (node (ref "C3R1") (pin "2") (pinfunction "2_2") (pintype "passive"))
      (node (ref "CON1") (pin "3") (pinfunction "3_3") (pintype "passive"))
      (node (ref "CON1") (pin "5") (pinfunction "5_5") (pintype "passive"))
      (node (ref "IC1") (pin "8") (pinfunction "GND_8") (pintype "power_in"))
      (node (ref "IC2") (pin "8") (pinfunction "GND_8") (pintype "power_in"))
      (node (ref "LED1") (pin "K") (pinfunction "C_K") (pintype "passive"))
      (node (ref "LED2") (pin "K") (pinfunction "C_K") (pintype "passive"))
      (node (ref "LED3") (pin "K") (pinfunction "C_K") (pintype "passive"))
      (node (ref "LED4") (pin "K") (pinfunction "C_K") (pintype "passive"))
      (node (ref "LED5") (pin "K") (pinfunction "C_K") (pintype "passive"))
      (node (ref "LED6") (pin "K") (pinfunction "C_K") (pintype "passive"))
      (node (ref "LED7") (pin "K") (pinfunction "C_K") (pintype "passive"))
      (node (ref "SV3") (pin "3") (pinfunction "3_3") (pintype "passive"))
      (node (ref "SV4") (pin "3") (pinfunction "3_3") (pintype "passive"))
      (node (ref "U2R") (pin "4") (pinfunction "GND_4") (pintype "power_in"))
      (node (ref "U3H") (pin "4") (pinfunction "GND_4") (pintype "power_in"))
      (node (ref "U4R") (pin "4") (pinfunction "GND_4") (pintype "power_in"))
      (node (ref "U5H") (pin "4") (pinfunction "GND_4") (pintype "power_in"))
      (node (ref "U5R") (pin "4") (pinfunction "GND_4") (pintype "power_in"))
      (node (ref "U6H") (pin "4") (pinfunction "GND_4") (pintype "power_in"))
      (node (ref "U7R") (pin "4") (pinfunction "GND_4") (pintype "power_in"))
      (node (ref "U8H") (pin "4") (pinfunction "GND_4") (pintype "power_in"))
    )
    (net (code "33") (name "Net-(6=5V-Pad1)") (class "Default")
      (node (ref "6=5V") (pin "1") (pinfunction "1_1") (pintype "passive"))
      (node (ref "CON1") (pin "6") (pinfunction "6_6") (pintype "passive"))
    )
    (net (code "34") (name "Net-(ABCD-S)") (class "Default")
      (node (ref "ABC") (pin "4") (pinfunction "S_4") (pintype "passive"))
      (node (ref "ABC3") (pin "1") (pinfunction "1_1") (pintype "passive"))
      (node (ref "ABC4") (pin "1") (pinfunction "1_1") (pintype "passive"))
      (node (ref "J7") (pin "4") (pinfunction "4_4") (pintype "passive"))
      (node (ref "NWS2") (pin "2") (pinfunction "2_2") (pintype "passive"))
      (node (ref "WS4") (pin "1") (pinfunction "1_1") (pintype "passive"))
    )
    (net (code "35") (name "Net-(D1-PadA)") (class "Default")
      (node (ref "D1") (pin "A") (pinfunction "A_A") (pintype "passive"))
      (node (ref "D2") (pin "C") (pinfunction "C_C") (pintype "passive"))
    )
    (net (code "36") (name "Net-(D2-PadA)") (class "Default")
      (node (ref "D2") (pin "A") (pinfunction "A_A") (pintype "passive"))
      (node (ref "D3") (pin "C") (pinfunction "C_C") (pintype "passive"))
    )
    (net (code "37") (name "Net-(D3-PadA)") (class "Default")
      (node (ref "D3") (pin "A") (pinfunction "A_A") (pintype "passive"))
      (node (ref "D4") (pin "C") (pinfunction "C_C") (pintype "passive"))
    )
    (net (code "38") (name "Net-(D4-PadA)") (class "Default")
      (node (ref "D4") (pin "A") (pinfunction "A_A") (pintype "passive"))
      (node (ref "D5") (pin "C") (pinfunction "C_C") (pintype "passive"))
    )
    (net (code "39") (name "Net-(D6-PadA)") (class "Default")
      (node (ref "D6") (pin "A") (pinfunction "A_A") (pintype "passive"))
      (node (ref "D7") (pin "C") (pinfunction "C_C") (pintype "passive"))
    )
    (net (code "40") (name "Net-(D7-PadA)") (class "Default")
      (node (ref "D7") (pin "A") (pinfunction "A_A") (pintype "passive"))
      (node (ref "D8") (pin "C") (pinfunction "C_C") (pintype "passive"))
    )
    (net (code "41") (name "Net-(D8-PadA)") (class "Default")
      (node (ref "D8") (pin "A") (pinfunction "A_A") (pintype "passive"))
      (node (ref "D9") (pin "C") (pinfunction "C_C") (pintype "passive"))
    )
    (net (code "42") (name "Net-(D10-PadC)") (class "Default")
      (node (ref "D10") (pin "C") (pinfunction "C_C") (pintype "passive"))
      (node (ref "D9") (pin "A") (pinfunction "A_A") (pintype "passive"))
    )
    (net (code "43") (name "Net-(IC1-I1)") (class "Default")
      (node (ref "IC1") (pin "1") (pinfunction "I1_1") (pintype "input"))
      (node (ref "RES_G1") (pin "2") (pinfunction "2_2") (pintype "passive"))
      (node (ref "RES_G2") (pin "1") (pinfunction "1_1") (pintype "passive"))
      (node (ref "RN1") (pin "8") (pinfunction "8_8") (pintype "passive"))
    )
    (net (code "44") (name "Net-(IC1-I3)") (class "Default")
      (node (ref "IC1") (pin "15") (pinfunction "O2_15") (pintype "open_collector"))
      (node (ref "IC1") (pin "3") (pinfunction "I3_3") (pintype "input"))
      (node (ref "RN1") (pin "6") (pinfunction "6_6") (pintype "passive"))
    )
    (net (code "45") (name "Net-(IC1-I5)") (class "Default")
      (node (ref "IC1") (pin "13") (pinfunction "O4_13") (pintype "open_collector"))
      (node (ref "IC1") (pin "5") (pinfunction "I5_5") (pintype "input"))
      (node (ref "RN1") (pin "4") (pinfunction "4_4") (pintype "passive"))
    )
    (net (code "46") (name "Net-(IC1-I7)") (class "Default")
      (node (ref "IC1") (pin "11") (pinfunction "O6_11") (pintype "open_collector"))
      (node (ref "IC1") (pin "7") (pinfunction "I7_7") (pintype "input"))
      (node (ref "RN1") (pin "2") (pinfunction "2_2") (pintype "passive"))
    )
    (net (code "47") (name "Net-(IC1-O1)") (class "Default")
      (node (ref "IC1") (pin "16") (pinfunction "O1_16") (pintype "open_collector"))
      (node (ref "IC2") (pin "1") (pinfunction "I1_1") (pintype "input"))
      (node (ref "RN2") (pin "8") (pinfunction "8_8") (pintype "passive"))
    )
    (net (code "48") (name "Net-(IC2-I3)") (class "Default")
      (node (ref "IC2") (pin "15") (pinfunction "O2_15") (pintype "open_collector"))
      (node (ref "IC2") (pin "3") (pinfunction "I3_3") (pintype "input"))
      (node (ref "RN2") (pin "6") (pinfunction "6_6") (pintype "passive"))
    )
    (net (code "49") (name "Net-(IC2-I5)") (class "Default")
      (node (ref "IC2") (pin "13") (pinfunction "O4_13") (pintype "open_collector"))
      (node (ref "IC2") (pin "5") (pinfunction "I5_5") (pintype "input"))
      (node (ref "RN2") (pin "4") (pinfunction "4_4") (pintype "passive"))
    )
    (net (code "50") (name "Net-(IC2-I7)") (class "Default")
      (node (ref "IC2") (pin "11") (pinfunction "O6_11") (pintype "open_collector"))
      (node (ref "IC2") (pin "7") (pinfunction "I7_7") (pintype "input"))
      (node (ref "RN2") (pin "2") (pinfunction "2_2") (pintype "passive"))
    )
    (net (code "51") (name "Net-(IC2-O1)") (class "Default")
      (node (ref "IC2") (pin "16") (pinfunction "O1_16") (pintype "open_collector"))
      (node (ref "K_RES_G") (pin "9") (pinfunction "2_9") (pintype "passive"))
    )
    (net (code "52") (name "Net-(K_RES_GB-O)") (class "Default")
      (node (ref "J8") (pin "1") (pinfunction "1_1") (pintype "passive"))
      (node (ref "K_RES_G") (pin "1") (pinfunction "O_1") (pintype "passive"))
      (node (ref "OUT_G") (pin "1") (pinfunction "S_1") (pintype "passive"))
      (node (ref "WS3") (pin "1") (pinfunction "1_1") (pintype "passive"))
    )
    (net (code "53") (name "Net-(K_RES_GB-S)") (class "Default")
      (node (ref "J8") (pin "3") (pinfunction "3_3") (pintype "passive"))
      (node (ref "K_RES_G") (pin "10") (pinfunction "S_10") (pintype "passive"))
      (node (ref "OUT_G") (pin "3") (pinfunction "S_3") (pintype "passive"))
    )
    (net (code "54") (name "Net-(K_RES_HA-2)") (class "Default")
      (node (ref "K_RES_H") (pin "9") (pinfunction "2_9") (pintype "passive"))
      (node (ref "RES_H") (pin "2") (pinfunction "2_2") (pintype "passive"))
    )
    (net (code "55") (name "Net-(K_RES_HB-O)") (class "Default")
      (node (ref "J9") (pin "1") (pinfunction "1_1") (pintype "passive"))
      (node (ref "K_RES_H") (pin "1") (pinfunction "O_1") (pintype "passive"))
      (node (ref "OUT_H") (pin "1") (pinfunction "S_1") (pintype "passive"))
    )
    (net (code "56") (name "Net-(K_RES_HB-S)") (class "Default")
      (node (ref "J9") (pin "3") (pinfunction "3_3") (pintype "passive"))
      (node (ref "K_RES_H") (pin "10") (pinfunction "S_10") (pintype "passive"))
      (node (ref "OUT_H") (pin "3") (pinfunction "S_3") (pintype "passive"))
    )
    (net (code "57") (name "Net-(LED1-PadA)") (class "Default")
      (node (ref "LED1") (pin "A") (pinfunction "A_A") (pintype "passive"))
      (node (ref "R4") (pin "1") (pinfunction "1_1") (pintype "passive"))
    )
    (net (code "58") (name "Net-(LED2-PadA)") (class "Default")
      (node (ref "LED2") (pin "A") (pinfunction "A_A") (pintype "passive"))
      (node (ref "R3") (pin "1") (pinfunction "1_1") (pintype "passive"))
    )
    (net (code "59") (name "Net-(LED3-PadA)") (class "Default")
      (node (ref "LED3") (pin "A") (pinfunction "A_A") (pintype "passive"))
      (node (ref "R5") (pin "1") (pinfunction "1_1") (pintype "passive"))
    )
    (net (code "60") (name "Net-(LED4-PadA)") (class "Default")
      (node (ref "LED4") (pin "A") (pinfunction "A_A") (pintype "passive"))
      (node (ref "R6") (pin "1") (pinfunction "1_1") (pintype "passive"))
    )
    (net (code "61") (name "Net-(LED5-PadA)") (class "Default")
      (node (ref "LED5") (pin "A") (pinfunction "A_A") (pintype "passive"))
      (node (ref "R7") (pin "1") (pinfunction "1_1") (pintype "passive"))
    )
    (net (code "62") (name "Net-(LED6-PadA)") (class "Default")
      (node (ref "LED6") (pin "A") (pinfunction "A_A") (pintype "passive"))
      (node (ref "R8") (pin "1") (pinfunction "1_1") (pintype "passive"))
    )
    (net (code "63") (name "Net-(LED7-PadA)") (class "Default")
      (node (ref "LED7") (pin "A") (pinfunction "A_A") (pintype "passive"))
      (node (ref "R9") (pin "2") (pinfunction "2_2") (pintype "passive"))
    )
    (net (code "64") (name "Net-(LED8-C)") (class "Default")
      (node (ref "LED8") (pin "K") (pinfunction "C_K") (pintype "passive"))
      (node (ref "R12") (pin "1") (pinfunction "1_1") (pintype "passive"))
    )
    (net (code "65") (name "Net-(LED9-C)") (class "Default")
      (node (ref "LED9") (pin "K") (pinfunction "C_K") (pintype "passive"))
      (node (ref "R13") (pin "1") (pinfunction "1_1") (pintype "passive"))
    )
    (net (code "66") (name "Net-(LED10-C)") (class "Default")
      (node (ref "LED10") (pin "K") (pinfunction "C_K") (pintype "passive"))
      (node (ref "R14") (pin "1") (pinfunction "1_1") (pintype "passive"))
    )
    (net (code "67") (name "Net-(LED11-C)") (class "Default")
      (node (ref "LED11") (pin "K") (pinfunction "C_K") (pintype "passive"))
      (node (ref "R15") (pin "1") (pinfunction "1_1") (pintype "passive"))
    )
    (net (code "68") (name "Net-(LED12-C)") (class "Default")
      (node (ref "LED12") (pin "K") (pinfunction "C_K") (pintype "passive"))
      (node (ref "R16") (pin "1") (pinfunction "1_1") (pintype "passive"))
    )
    (net (code "69") (name "Net-(LED13-C)") (class "Default")
      (node (ref "LED13") (pin "K") (pinfunction "C_K") (pintype "passive"))
      (node (ref "R17") (pin "1") (pinfunction "1_1") (pintype "passive"))
    )
    (net (code "70") (name "Net-(OUT_GB-S)") (class "Default")
      (node (ref "J8") (pin "2") (pinfunction "2_2") (pintype "passive"))
      (node (ref "K_RES_G") (pin "5") (pinfunction "P_5") (pintype "passive"))
      (node (ref "K_RES_G") (pin "6") (pinfunction "P_6") (pintype "passive"))
      (node (ref "OUT_G") (pin "2") (pinfunction "S_2") (pintype "passive"))
      (node (ref "WS4") (pin "2") (pinfunction "2_2") (pintype "passive"))
    )
    (net (code "71") (name "Net-(OUT_HB-S)") (class "Default")
      (node (ref "J9") (pin "2") (pinfunction "2_2") (pintype "passive"))
      (node (ref "K_RES_H") (pin "5") (pinfunction "P_5") (pintype "passive"))
      (node (ref "K_RES_H") (pin "6") (pinfunction "P_6") (pintype "passive"))
      (node (ref "OUT_H") (pin "2") (pinfunction "S_2") (pintype "passive"))
    )
    (net (code "72") (name "Net-(SV3-Pad2)") (class "Default")
      (node (ref "SV3") (pin "2") (pinfunction "2_2") (pintype "passive"))
      (node (ref "TERM") (pin "2") (pinfunction "2_2") (pintype "passive"))
    )
    (net (code "73") (name "Net-(U2R-DIN)") (class "Default")
      (node (ref "CON1") (pin "2") (pinfunction "2_2") (pintype "passive"))
      (node (ref "SV4") (pin "2") (pinfunction "2_2") (pintype "passive"))
      (node (ref "U2R") (pin "6") (pinfunction "DIN_6") (pintype "input"))
      (node (ref "U3H") (pin "6") (pinfunction "DIN_6") (pintype "input"))
    )
    (net (code "74") (name "Net-(U2R-DO)") (class "Default")
      (node (ref "SINGLE") (pin "2") (pinfunction "2_2") (pintype "passive"))
      (node (ref "U2R") (pin "5") (pinfunction "DO_5") (pintype "output"))
      (node (ref "U3H") (pin "5") (pinfunction "DO_5") (pintype "output"))
      (node (ref "U4R") (pin "6") (pinfunction "DIN_6") (pintype "input"))
      (node (ref "U5H") (pin "6") (pinfunction "DIN_6") (pintype "input"))
    )
    (net (code "75") (name "Net-(U2R-VDD)") (class "Default")
      (node (ref "C1H") (pin "1") (pinfunction "1_1") (pintype "passive"))
      (node (ref "C1R") (pin "1") (pinfunction "1_1") (pintype "passive"))
      (node (ref "R1") (pin "2") (pinfunction "2_2") (pintype "passive"))
      (node (ref "U2R") (pin "8") (pinfunction "VDD_8") (pintype "power_in"))
      (node (ref "U3H") (pin "8") (pinfunction "VDD_8") (pintype "power_in"))
    )
    (net (code "76") (name "Net-(U4R-DO)") (class "Default")
      (node (ref "NO_OPTW1") (pin "2") (pinfunction "2_2") (pintype "passive"))
      (node (ref "SINGLE") (pin "1") (pinfunction "1_1") (pintype "passive"))
      (node (ref "U4R") (pin "5") (pinfunction "DO_5") (pintype "output"))
      (node (ref "U5H") (pin "5") (pinfunction "DO_5") (pintype "output"))
      (node (ref "U5R") (pin "6") (pinfunction "DIN_6") (pintype "input"))
      (node (ref "U6H") (pin "6") (pinfunction "DIN_6") (pintype "input"))
    )
    (net (code "77") (name "Net-(U4R-VDD)") (class "Default")
      (node (ref "C2H") (pin "1") (pinfunction "1_1") (pintype "passive"))
      (node (ref "C2R") (pin "1") (pinfunction "1_1") (pintype "passive"))
      (node (ref "R2") (pin "2") (pinfunction "2_2") (pintype "passive"))
      (node (ref "U4R") (pin "8") (pinfunction "VDD_8") (pintype "power_in"))
      (node (ref "U5H") (pin "8") (pinfunction "VDD_8") (pintype "power_in"))
    )
    (net (code "78") (name "Net-(U5R-DO)") (class "Default")
      (node (ref "NO_OPTW1") (pin "1") (pinfunction "1_1") (pintype "passive"))
      (node (ref "NO_OPTW2") (pin "2") (pinfunction "2_2") (pintype "passive"))
      (node (ref "U5R") (pin "5") (pinfunction "DO_5") (pintype "output"))
      (node (ref "U6H") (pin "5") (pinfunction "DO_5") (pintype "output"))
      (node (ref "U7R") (pin "6") (pinfunction "DIN_6") (pintype "input"))
      (node (ref "U8H") (pin "6") (pinfunction "DIN_6") (pintype "input"))
    )
    (net (code "79") (name "Net-(U5R-OUTB)") (class "Default")
      (node (ref "OPT_LED") (pin "4") (pinfunction "4_4") (pintype "passive"))
      (node (ref "U5R") (pin "3") (pinfunction "OUTB_3") (pintype "open_collector"))
      (node (ref "U6H") (pin "3") (pinfunction "OUTB_3") (pintype "open_collector"))
    )
    (net (code "80") (name "Net-(U5R-OUTG)") (class "Default")
      (node (ref "OPT_LED") (pin "3") (pinfunction "3_3") (pintype "passive"))
      (node (ref "U5R") (pin "2") (pinfunction "OUTG_2") (pintype "open_collector"))
      (node (ref "U6H") (pin "2") (pinfunction "OUTG_2") (pintype "open_collector"))
    )
    (net (code "81") (name "Net-(U5R-OUTR)") (class "Default")
      (node (ref "OPT_LED") (pin "2") (pinfunction "2_2") (pintype "passive"))
      (node (ref "RES_G1") (pin "1") (pinfunction "1_1") (pintype "passive"))
      (node (ref "U5R") (pin "1") (pinfunction "OUTR_1") (pintype "open_collector"))
      (node (ref "U6H") (pin "1") (pinfunction "OUTR_1") (pintype "open_collector"))
    )
    (net (code "82") (name "Net-(U5R-VDD)") (class "Default")
      (node (ref "C3H") (pin "1") (pinfunction "1_1") (pintype "passive"))
      (node (ref "C3R") (pin "1") (pinfunction "1_1") (pintype "passive"))
      (node (ref "R10") (pin "2") (pinfunction "2_2") (pintype "passive"))
      (node (ref "U5R") (pin "8") (pinfunction "VDD_8") (pintype "power_in"))
      (node (ref "U6H") (pin "8") (pinfunction "VDD_8") (pintype "power_in"))
    )
    (net (code "83") (name "Net-(U7R-DO)") (class "Default")
      (node (ref "CON1") (pin "4") (pinfunction "4_4") (pintype "passive"))
      (node (ref "NO_OPTW2") (pin "1") (pinfunction "1_1") (pintype "passive"))
      (node (ref "SV3") (pin "4") (pinfunction "4_4") (pintype "passive"))
      (node (ref "SV4") (pin "4") (pinfunction "4_4") (pintype "passive"))
      (node (ref "TERM") (pin "1") (pinfunction "1_1") (pintype "passive"))
      (node (ref "U7R") (pin "5") (pinfunction "DO_5") (pintype "output"))
      (node (ref "U8H") (pin "5") (pinfunction "DO_5") (pintype "output"))
    )
    (net (code "84") (name "Net-(U7R-OUTB)") (class "Default")
      (node (ref "OPT_LED") (pin "8") (pinfunction "8_8") (pintype "passive"))
      (node (ref "U7R") (pin "3") (pinfunction "OUTB_3") (pintype "open_collector"))
      (node (ref "U8H") (pin "3") (pinfunction "OUTB_3") (pintype "open_collector"))
    )
    (net (code "85") (name "Net-(U7R-OUTG)") (class "Default")
      (node (ref "OPT_LED") (pin "7") (pinfunction "7_7") (pintype "passive"))
      (node (ref "U7R") (pin "2") (pinfunction "OUTG_2") (pintype "open_collector"))
      (node (ref "U8H") (pin "2") (pinfunction "OUTG_2") (pintype "open_collector"))
    )
    (net (code "86") (name "Net-(U7R-OUTR)") (class "Default")
      (node (ref "OPT_LED") (pin "6") (pinfunction "6_6") (pintype "passive"))
      (node (ref "U7R") (pin "1") (pinfunction "OUTR_1") (pintype "open_collector"))
      (node (ref "U8H") (pin "1") (pinfunction "OUTR_1") (pintype "open_collector"))
    )
    (net (code "87") (name "Net-(U7R-VDD)") (class "Default")
      (node (ref "C3H1") (pin "1") (pinfunction "1_1") (pintype "passive"))
      (node (ref "C3R1") (pin "1") (pinfunction "1_1") (pintype "passive"))
      (node (ref "R11") (pin "2") (pinfunction "2_2") (pintype "passive"))
      (node (ref "U7R") (pin "8") (pinfunction "VDD_8") (pintype "power_in"))
      (node (ref "U8H") (pin "8") (pinfunction "VDD_8") (pintype "power_in"))
    )
    (net (code "88") (name "unconnected-(U2R-SET-Pad7)") (class "Default")
      (node (ref "U2R") (pin "7") (pinfunction "SET_7") (pintype "bidirectional"))
    )
    (net (code "89") (name "unconnected-(U3H-SET-Pad7)") (class "Default")
      (node (ref "U3H") (pin "7") (pinfunction "SET_7") (pintype "bidirectional"))
    )
    (net (code "90") (name "unconnected-(U4R-SET-Pad7)") (class "Default")
      (node (ref "U4R") (pin "7") (pinfunction "SET_7") (pintype "bidirectional"))
    )
    (net (code "91") (name "unconnected-(U5H-SET-Pad7)") (class "Default")
      (node (ref "U5H") (pin "7") (pinfunction "SET_7") (pintype "bidirectional"))
    )
    (net (code "92") (name "unconnected-(U5R-SET-Pad7)") (class "Default")
      (node (ref "U5R") (pin "7") (pinfunction "SET_7") (pintype "bidirectional"))
    )
    (net (code "93") (name "unconnected-(U6H-SET-Pad7)") (class "Default")
      (node (ref "U6H") (pin "7") (pinfunction "SET_7") (pintype "bidirectional"))
    )
    (net (code "94") (name "unconnected-(U7R-SET-Pad7)") (class "Default")
      (node (ref "U7R") (pin "7") (pinfunction "SET_7") (pintype "bidirectional"))
    )
    (net (code "95") (name "unconnected-(U8H-SET-Pad7)") (class "Default")
      (node (ref "U8H") (pin "7") (pinfunction "SET_7") (pintype "bidirectional"))
    )
  )
)
